# Sanity0.net
KiCad netlist of a schematic drawn in Altium Designer
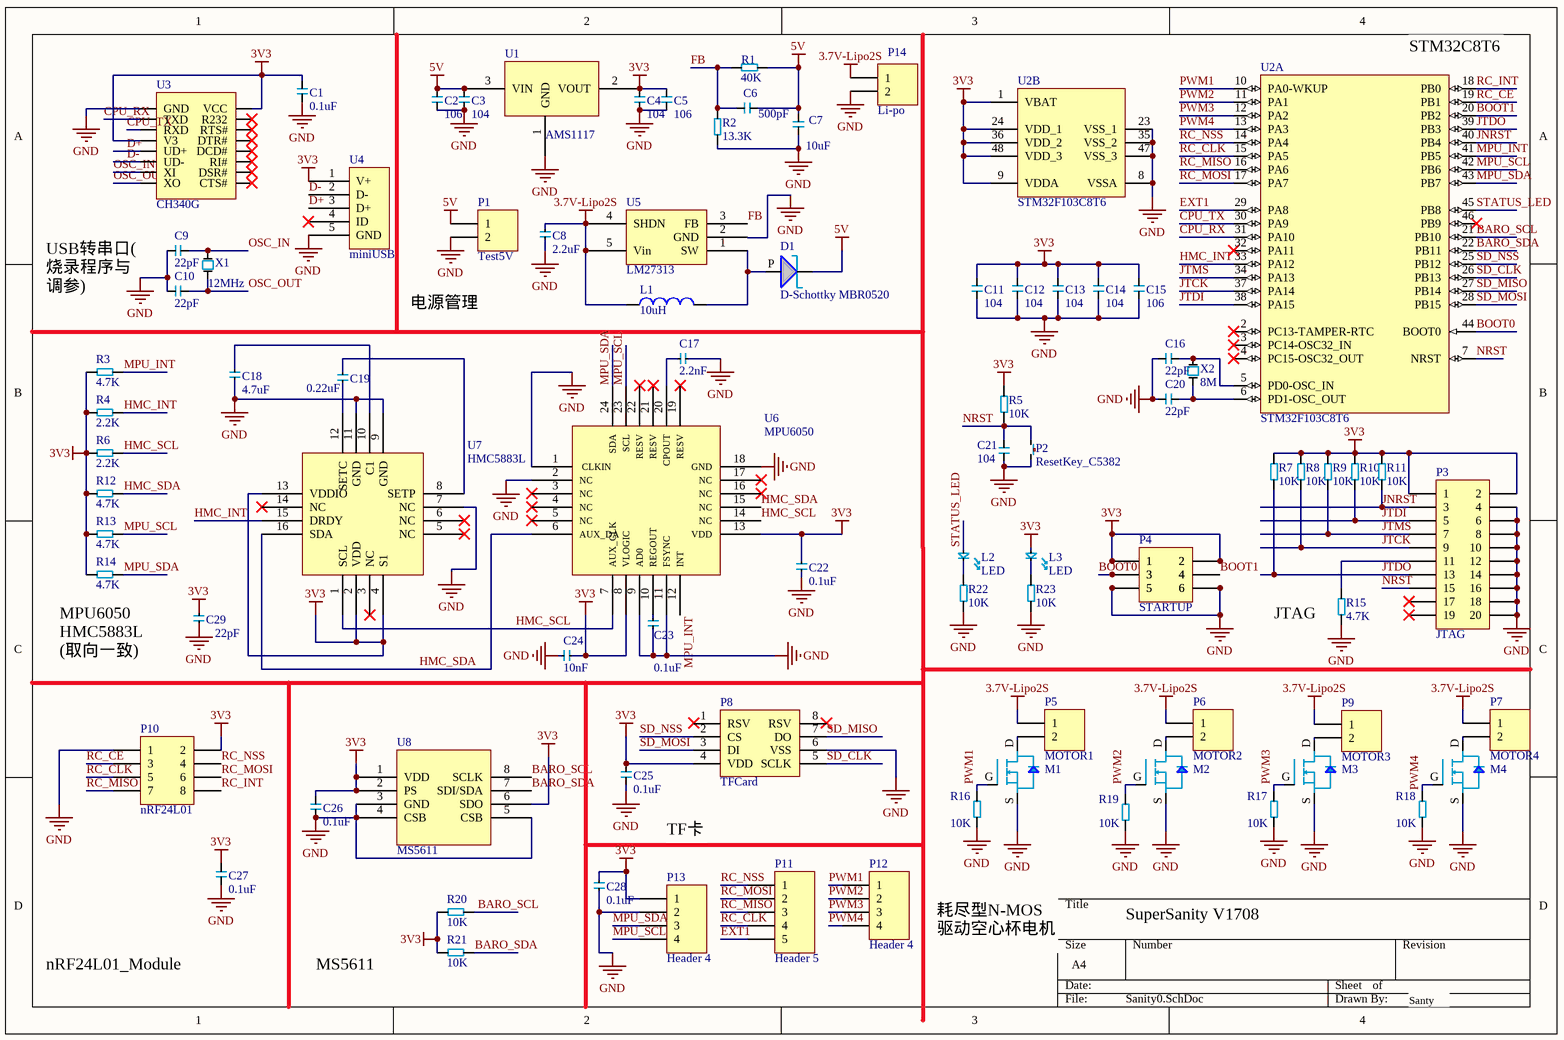
[diagram p0: Sanity0.SchDoc]

(export (version "E")
  (design (tool "Eeschema 10.0.6"))
  (components
    (comp (ref "C1") (value "0.1uF") (footprint "LC-0402") (libsource (lib "0402") (part "Cap-0402")))
    (comp (ref "C2") (value "106") (footprint "LC-0402") (libsource (lib "0402") (part "Cap-0402")))
    (comp (ref "C3") (value "104") (footprint "LC-0402") (libsource (lib "0402") (part "Cap-0402")))
    (comp (ref "C4") (value "104") (footprint "LC-0402") (libsource (lib "0402") (part "Cap-0402")))
    (comp (ref "C5") (value "106") (footprint "LC-0402") (libsource (lib "0402") (part "Cap-0402")))
    (comp (ref "C6") (value "500pF") (footprint "LC-0402") (libsource (lib "0402") (part "Cap-0402")))
    (comp (ref "C7") (value "10uF") (footprint "LC-0402") (libsource (lib "0402") (part "Cap-0402")))
    (comp (ref "C8") (value "2.2uF") (footprint "Cap-0603") (libsource (lib "Cap-0603") (part "Cap0603")))
    (comp (ref "C9") (value "22pF") (footprint "LC-0402") (libsource (lib "0402") (part "Cap-0402")))
    (comp (ref "C10") (value "22pF") (footprint "LC-0402") (libsource (lib "0402") (part "Cap-0402")))
    (comp (ref "C11") (value "104") (footprint "LC-0402") (libsource (lib "0402") (part "Cap-0402")))
    (comp (ref "C12") (value "104") (footprint "LC-0402") (libsource (lib "0402") (part "Cap-0402")))
    (comp (ref "C13") (value "104") (footprint "LC-0402") (libsource (lib "0402") (part "Cap-0402")))
    (comp (ref "C14") (value "104") (footprint "LC-0402") (libsource (lib "0402") (part "Cap-0402")))
    (comp (ref "C15") (value "106") (footprint "LC-0402") (libsource (lib "0402") (part "Cap-0402")))
    (comp (ref "C16") (value "22pF") (footprint "LC-0402") (libsource (lib "0402") (part "Cap-0402")))
    (comp (ref "C17") (value "2.2nF") (footprint "Cap-0603") (libsource (lib "Cap-0603") (part "Cap0603")))
    (comp (ref "C18") (value "4.7uF") (footprint "Cap-0603") (libsource (lib "Cap-0603") (part "Cap0603")))
    (comp (ref "C19") (value "0.22uF") (footprint "Cap-0603") (libsource (lib "Cap-0603") (part "Cap0603")))
    (comp (ref "C20") (value "22pF") (footprint "LC-0402") (libsource (lib "0402") (part "Cap-0402")))
    (comp (ref "C21") (value "104") (footprint "LC-0402") (libsource (lib "0402") (part "Cap-0402")))
    (comp (ref "C22") (value "0.1uF") (footprint "Cap-0603") (libsource (lib "Cap-0603") (part "Cap0603")))
    (comp (ref "C23") (value "0.1uF") (footprint "Cap-0603") (libsource (lib "Cap-0603") (part "Cap0603")))
    (comp (ref "C24") (value "10nF") (footprint "Cap-0603") (libsource (lib "Cap-0603") (part "Cap0603")))
    (comp (ref "C25") (value "0.1uF") (footprint "LC-0402") (libsource (lib "0402") (part "Cap-0402")))
    (comp (ref "C26") (value "0.1uF") (footprint "LC-0402") (libsource (lib "0402") (part "Cap-0402")))
    (comp (ref "C27") (value "0.1uF") (footprint "LC-0402") (libsource (lib "0402") (part "Cap-0402")))
    (comp (ref "C28") (value "0.1uF") (footprint "Cap-0603") (libsource (lib "Cap-0603") (part "Cap0603")))
    (comp (ref "C29") (value "22pF") (footprint "Cap-0603") (libsource (lib "Cap-0603") (part "Cap0603")))
    (comp (ref "D1")
      (value "D-Schottky MBR0520")
      (footprint "SOD123")
      (libsource (lib "D-Schottky-MBR0520") (part "D-Schottky MBR0520"))
    )
    (comp (ref "L1")
      (value "10uH")
      (footprint "INDC1608L")
      (description "Inductor")
      (fields (field (name "PUBLISHER") "Altium Limited"))
      (libsource (lib "Miscellaneous Devices") (part "Inductor"))
    )
    (comp (ref "L2") (value "LED") (footprint "0603_LED_S1") (libsource (lib "LED_0603") (part "LED")))
    (comp (ref "L3") (value "LED") (footprint "0603_LED_S1") (libsource (lib "LED_0603") (part "LED")))
    (comp (ref "M1")
      (value "SI2302-NMOS")
      (footprint "SOT-23(SOT-23-3)")
      (libsource (lib "SI2303-NMOS") (part "SI2302-NMOS"))
    )
    (comp (ref "M2")
      (value "SI2302-NMOS")
      (footprint "SOT-23(SOT-23-3)")
      (libsource (lib "SI2303-NMOS") (part "SI2302-NMOS"))
    )
    (comp (ref "M3")
      (value "SI2302-NMOS")
      (footprint "SOT-23(SOT-23-3)")
      (libsource (lib "SI2303-NMOS") (part "SI2302-NMOS"))
    )
    (comp (ref "M4")
      (value "SI2302-NMOS")
      (footprint "SOT-23(SOT-23-3)")
      (libsource (lib "SI2303-NMOS") (part "SI2302-NMOS"))
    )
    (comp (ref "P1")
      (value "Test5V")
      (footprint "HDR1X2")
      (description "Header, 2-Pin")
      (fields (field (name "PUBLISHER") "Altium Limited"))
      (libsource (lib "Miscellaneous Connectors") (part "Header 2"))
    )
    (comp (ref "P2")
      (value "ResetKey_C5382")
      (footprint "ResetKeyC5382")
      (libsource (lib "ResetKey_C5382") (part "ResetKey_C5382"))
    )
    (comp (ref "P3")
      (value "JTAG")
      (footprint "HDR2X10")
      (description "Header, 10-Pin, Dual row")
      (fields (field (name "PUBLISHER") "Altium Limited"))
      (libsource (lib "Miscellaneous Connectors") (part "Header 10X2"))
    )
    (comp (ref "P4")
      (value "STARTUP")
      (footprint "HDR2X3")
      (description "Header, 3-Pin, Dual row")
      (fields (field (name "PUBLISHER") "Altium Limited"))
      (libsource (lib "Miscellaneous Connectors") (part "Header 3X2"))
    )
    (comp (ref "P5")
      (value "MOTOR1")
      (footprint "HDR1X2")
      (description "Header, 2-Pin")
      (fields (field (name "PUBLISHER") "Altium Limited"))
      (libsource (lib "Miscellaneous Connectors") (part "Header 2"))
    )
    (comp (ref "P6")
      (value "MOTOR2")
      (footprint "HDR1X2")
      (description "Header, 2-Pin")
      (fields (field (name "PUBLISHER") "Altium Limited"))
      (libsource (lib "Miscellaneous Connectors") (part "Header 2"))
    )
    (comp (ref "P7")
      (value "MOTOR4")
      (footprint "HDR1X2")
      (description "Header, 2-Pin")
      (fields (field (name "PUBLISHER") "Altium Limited"))
      (libsource (lib "Miscellaneous Connectors") (part "Header 2"))
    )
    (comp (ref "P8") (value "TFCard") (footprint "TF_card") (libsource (lib "TF_card") (part "TFCard")))
    (comp (ref "P9")
      (value "MOTOR3")
      (footprint "HDR1X2")
      (description "Header, 2-Pin")
      (fields (field (name "PUBLISHER") "Altium Limited"))
      (libsource (lib "Miscellaneous Connectors") (part "Header 2"))
    )
    (comp (ref "P10")
      (value "nRF24L01")
      (footprint "HDR2X4")
      (description "Header, 4-Pin, Dual row")
      (fields (field (name "PUBLISHER") "Altium Limited"))
      (libsource (lib "Miscellaneous Connectors") (part "Header 4X2"))
    )
    (comp (ref "P11")
      (value "Header 5")
      (footprint "HDR1X5")
      (description "Header, 5-Pin")
      (fields (field (name "PUBLISHER") "Altium Limited"))
      (libsource (lib "Miscellaneous Connectors") (part "Header 5"))
    )
    (comp (ref "P12")
      (value "Header 4")
      (footprint "HDR1X4")
      (description "Header, 4-Pin")
      (fields (field (name "PUBLISHER") "Altium Limited"))
      (libsource (lib "Miscellaneous Connectors") (part "Header 4"))
    )
    (comp (ref "P13")
      (value "Header 4")
      (footprint "HDR1X4")
      (description "Header, 4-Pin")
      (fields (field (name "PUBLISHER") "Altium Limited"))
      (libsource (lib "Miscellaneous Connectors") (part "Header 4"))
    )
    (comp (ref "P14")
      (value "Li-po")
      (footprint "HDR1X2")
      (description "Header, 2-Pin")
      (fields (field (name "PUBLISHER") "Altium Limited"))
      (libsource (lib "Miscellaneous Connectors") (part "Header 2"))
    )
    (comp (ref "R1") (value "40K") (footprint "Res-0402") (libsource (lib "0402-Res") (part "Res-0402")))
    (comp (ref "R2") (value "13.3K") (footprint "Res-0402") (libsource (lib "0402-Res") (part "Res-0402")))
    (comp (ref "R3") (value "4.7K") (footprint "Res-0402") (libsource (lib "0402-Res") (part "Res-0402")))
    (comp (ref "R4") (value "2.2K") (footprint "Res-0402") (libsource (lib "0402-Res") (part "Res-0402")))
    (comp (ref "R5") (value "10K") (footprint "Res-0402") (libsource (lib "0402-Res") (part "Res-0402")))
    (comp (ref "R6") (value "2.2K") (footprint "Res-0402") (libsource (lib "0402-Res") (part "Res-0402")))
    (comp (ref "R7") (value "10K") (footprint "Res-0402") (libsource (lib "0402-Res") (part "Res-0402")))
    (comp (ref "R8") (value "10K") (footprint "Res-0402") (libsource (lib "0402-Res") (part "Res-0402")))
    (comp (ref "R9") (value "10K") (footprint "Res-0402") (libsource (lib "0402-Res") (part "Res-0402")))
    (comp (ref "R10") (value "10K") (footprint "Res-0402") (libsource (lib "0402-Res") (part "Res-0402")))
    (comp (ref "R11") (value "10K") (footprint "Res-0402") (libsource (lib "0402-Res") (part "Res-0402")))
    (comp (ref "R12") (value "4.7K") (footprint "Res-0402") (libsource (lib "0402-Res") (part "Res-0402")))
    (comp (ref "R13") (value "4.7K") (footprint "Res-0402") (libsource (lib "0402-Res") (part "Res-0402")))
    (comp (ref "R14") (value "4.7K") (footprint "Res-0402") (libsource (lib "0402-Res") (part "Res-0402")))
    (comp (ref "R15") (value "4.7K") (footprint "Res-0402") (libsource (lib "0402-Res") (part "Res-0402")))
    (comp (ref "R16") (value "10K") (footprint "Res-0402") (libsource (lib "0402-Res") (part "Res-0402")))
    (comp (ref "R17") (value "10K") (footprint "Res-0402") (libsource (lib "0402-Res") (part "Res-0402")))
    (comp (ref "R18") (value "10K") (footprint "Res-0402") (libsource (lib "0402-Res") (part "Res-0402")))
    (comp (ref "R19") (value "10K") (footprint "Res-0402") (libsource (lib "0402-Res") (part "Res-0402")))
    (comp (ref "R20") (value "10K") (footprint "Res-0402") (libsource (lib "0402-Res") (part "Res-0402")))
    (comp (ref "R21") (value "10K") (footprint "Res-0402") (libsource (lib "0402-Res") (part "Res-0402")))
    (comp (ref "R22") (value "10K") (footprint "Res-0402") (libsource (lib "0402-Res") (part "Res-0402")))
    (comp (ref "R23") (value "10K") (footprint "Res-0402") (libsource (lib "0402-Res") (part "Res-0402")))
    (comp (ref "U1") (value "AMS1117") (footprint "AMS1117") (libsource (lib "AMS1117") (part "AMS1117")))
    (comp (ref "U2")
      (value "STM32F103C8T6")
      (footprint "STM-LQFP48_N")
      (libsource (lib "STMicroelectronics STM32 F1") (part "STM32F103C8T6"))
    )
    (comp (ref "U3")
      (value "CH340G")
      (footprint "LC-SOP-16_150mil")
      (libsource (lib "CH340G") (part "CH340G"))
    )
    (comp (ref "U4") (value "miniUSB") (footprint "miniUSB") (libsource (lib "miniUSB") (part "miniUSB")))
    (comp (ref "U5") (value "LM27313") (footprint "LM27313") (libsource (lib "LM27313") (part "LM27313")))
    (comp (ref "U6") (value "MPU6050") (footprint "MPU6050") (libsource (lib "MPU6050") (part "MPU6050")))
    (comp (ref "U7")
      (value "HMC5883L")
      (footprint "LCCS50P300X300X90-16N-1")
      (libsource (lib "HMC5883L") (part "HMC5883L"))
    )
    (comp (ref "U8") (value "MS5611") (footprint "MS5611") (libsource (lib "MS5611") (part "MS5611")))
    (comp (ref "X1") (value "12MHz") (footprint "LC-HC-49SMD") (libsource (lib "49SMD-8M") (part "49SMD")))
    (comp (ref "X2") (value "8M") (footprint "LC-HC-49SMD") (libsource (lib "49SMD-8M") (part "49SMD")))
  )
  (nets
    (net (code "1") (name "/BARO_SCL") (class "Default")
      (node (ref "R20") (pin "1") (pinfunction "1_1") (pintype "passive"))
      (node (ref "U2") (pin "21") (pinfunction "PB10_21") (pintype "bidirectional"))
      (node (ref "U8") (pin "8") (pinfunction "SCLK_8") (pintype "passive"))
    )
    (net (code "2") (name "/BARO_SDA") (class "Default")
      (node (ref "R21") (pin "1") (pinfunction "1_1") (pintype "passive"))
      (node (ref "U2") (pin "22") (pinfunction "PB11_22") (pintype "bidirectional"))
      (node (ref "U8") (pin "7") (pinfunction "SDI/SDA_7") (pintype "passive"))
    )
    (net (code "3") (name "/BOOT0") (class "Default")
      (node (ref "P4") (pin "3") (pinfunction "3_3") (pintype "passive"))
      (node (ref "U2") (pin "44") (pinfunction "BOOT0_44") (pintype "input"))
    )
    (net (code "4") (name "/BOOT1") (class "Default")
      (node (ref "P4") (pin "4") (pinfunction "4_4") (pintype "passive"))
      (node (ref "U2") (pin "20") (pinfunction "PB2_20") (pintype "bidirectional"))
    )
    (net (code "5") (name "/CPU_RX") (class "Default")
      (node (ref "U2") (pin "31") (pinfunction "PA10_31") (pintype "bidirectional"))
      (node (ref "U3") (pin "2") (pinfunction "TXD_2") (pintype "passive"))
    )
    (net (code "6") (name "/CPU_TX") (class "Default")
      (node (ref "U2") (pin "30") (pinfunction "PA9_30") (pintype "bidirectional"))
      (node (ref "U3") (pin "3") (pinfunction "RXD_3") (pintype "passive"))
    )
    (net (code "7") (name "/D+") (class "Default")
      (node (ref "U3") (pin "5") (pinfunction "UD+_5") (pintype "passive"))
      (node (ref "U4") (pin "3") (pinfunction "D+_3") (pintype "passive"))
    )
    (net (code "8") (name "/D-") (class "Default")
      (node (ref "U3") (pin "6") (pinfunction "UD-_6") (pintype "passive"))
      (node (ref "U4") (pin "2") (pinfunction "D-_2") (pintype "passive"))
    )
    (net (code "9") (name "/EXT1") (class "Default")
      (node (ref "P11") (pin "5") (pinfunction "5_5") (pintype "passive"))
      (node (ref "U2") (pin "29") (pinfunction "PA8_29") (pintype "bidirectional"))
    )
    (net (code "10") (name "/FB") (class "Default")
      (node (ref "C6") (pin "0") (pinfunction "0_0") (pintype "passive"))
      (node (ref "R1") (pin "1") (pinfunction "1_1") (pintype "passive"))
      (node (ref "R2") (pin "0") (pinfunction "0_0") (pintype "passive"))
      (node (ref "U5") (pin "3") (pinfunction "FB_3") (pintype "passive"))
    )
    (net (code "11") (name "/HMC_INT") (class "Default")
      (node (ref "R4") (pin "1") (pinfunction "1_1") (pintype "passive"))
      (node (ref "U2") (pin "33") (pinfunction "PA12_33") (pintype "bidirectional"))
      (node (ref "U7") (pin "15") (pinfunction "DRDY_15") (pintype "passive"))
    )
    (net (code "12") (name "/HMC_SCL") (class "Default")
      (node (ref "R6") (pin "1") (pinfunction "1_1") (pintype "passive"))
      (node (ref "U6") (pin "14") (pinfunction "NC_14") (pintype "passive"))
      (node (ref "U6") (pin "7") (pinfunction "AUX_CLK_7") (pintype "passive"))
      (node (ref "U7") (pin "1") (pinfunction "SCL_1") (pintype "passive"))
    )
    (net (code "13") (name "/HMC_SDA") (class "Default")
      (node (ref "R12") (pin "1") (pinfunction "1_1") (pintype "passive"))
      (node (ref "U6") (pin "15") (pinfunction "NC_15") (pintype "passive"))
      (node (ref "U6") (pin "6") (pinfunction "AUX_DA_6") (pintype "passive"))
      (node (ref "U7") (pin "16") (pinfunction "SDA_16") (pintype "passive"))
    )
    (net (code "14") (name "/JNRST") (class "Default")
      (node (ref "P3") (pin "3") (pinfunction "3_3") (pintype "passive"))
      (node (ref "R11") (pin "1") (pinfunction "1_1") (pintype "passive"))
      (node (ref "U2") (pin "40") (pinfunction "PB4_40") (pintype "bidirectional"))
    )
    (net (code "15") (name "/JTCK") (class "Default")
      (node (ref "P3") (pin "9") (pinfunction "9_9") (pintype "passive"))
      (node (ref "R8") (pin "1") (pinfunction "1_1") (pintype "passive"))
      (node (ref "U2") (pin "37") (pinfunction "PA14_37") (pintype "bidirectional"))
    )
    (net (code "16") (name "/JTDI") (class "Default")
      (node (ref "P3") (pin "5") (pinfunction "5_5") (pintype "passive"))
      (node (ref "R10") (pin "1") (pinfunction "1_1") (pintype "passive"))
      (node (ref "U2") (pin "38") (pinfunction "PA15_38") (pintype "bidirectional"))
    )
    (net (code "17") (name "/JTDO") (class "Default")
      (node (ref "P3") (pin "13") (pinfunction "13_13") (pintype "passive"))
      (node (ref "R7") (pin "1") (pinfunction "1_1") (pintype "passive"))
      (node (ref "U2") (pin "39") (pinfunction "PB3_39") (pintype "bidirectional"))
    )
    (net (code "18") (name "/JTMS") (class "Default")
      (node (ref "P3") (pin "7") (pinfunction "7_7") (pintype "passive"))
      (node (ref "R9") (pin "1") (pinfunction "1_1") (pintype "passive"))
      (node (ref "U2") (pin "34") (pinfunction "PA13_34") (pintype "bidirectional"))
    )
    (net (code "19") (name "/MPU_INT") (class "Default")
      (node (ref "R3") (pin "1") (pinfunction "1_1") (pintype "passive"))
      (node (ref "U2") (pin "41") (pinfunction "PB5_41") (pintype "bidirectional"))
      (node (ref "U6") (pin "12") (pinfunction "INT_12") (pintype "passive"))
    )
    (net (code "20") (name "/MPU_SCL") (class "Default")
      (node (ref "P13") (pin "4") (pinfunction "4_4") (pintype "passive"))
      (node (ref "R13") (pin "1") (pinfunction "1_1") (pintype "passive"))
      (node (ref "U2") (pin "42") (pinfunction "PB6_42") (pintype "bidirectional"))
      (node (ref "U6") (pin "23") (pinfunction "SCL_23") (pintype "passive"))
    )
    (net (code "21") (name "/MPU_SDA") (class "Default")
      (node (ref "P13") (pin "3") (pinfunction "3_3") (pintype "passive"))
      (node (ref "R14") (pin "1") (pinfunction "1_1") (pintype "passive"))
      (node (ref "U2") (pin "43") (pinfunction "PB7_43") (pintype "bidirectional"))
      (node (ref "U6") (pin "24") (pinfunction "SDA_24") (pintype "passive"))
    )
    (net (code "22") (name "/NRST") (class "Default")
      (node (ref "C21") (pin "1") (pinfunction "1_1") (pintype "passive"))
      (node (ref "P2") (pin "1") (pinfunction "1_1") (pintype "passive"))
      (node (ref "P3") (pin "15") (pinfunction "15_15") (pintype "passive"))
      (node (ref "R5") (pin "1") (pinfunction "1_1") (pintype "passive"))
      (node (ref "U2") (pin "7") (pinfunction "NRST_7") (pintype "bidirectional"))
    )
    (net (code "23") (name "/OSC_IN") (class "Default")
      (node (ref "C9") (pin "0") (pinfunction "0_0") (pintype "passive"))
      (node (ref "U3") (pin "7") (pinfunction "XI_7") (pintype "passive"))
      (node (ref "X1") (pin "0") (pinfunction "0_0") (pintype "passive"))
    )
    (net (code "24") (name "/OSC_OUT") (class "Default")
      (node (ref "C10") (pin "0") (pinfunction "0_0") (pintype "passive"))
      (node (ref "U3") (pin "8") (pinfunction "XO_8") (pintype "passive"))
      (node (ref "X1") (pin "1") (pinfunction "1_1") (pintype "passive"))
    )
    (net (code "25") (name "/PWM1") (class "Default")
      (node (ref "M1") (pin "G") (pinfunction "2_G") (pintype "passive"))
      (node (ref "P12") (pin "1") (pinfunction "1_1") (pintype "passive"))
      (node (ref "R16") (pin "0") (pinfunction "0_0") (pintype "passive"))
      (node (ref "U2") (pin "10") (pinfunction "PA0-WKUP_10") (pintype "bidirectional"))
    )
    (net (code "26") (name "/PWM2") (class "Default")
      (node (ref "M2") (pin "G") (pinfunction "2_G") (pintype "passive"))
      (node (ref "P12") (pin "2") (pinfunction "2_2") (pintype "passive"))
      (node (ref "R19") (pin "1") (pinfunction "1_1") (pintype "passive"))
      (node (ref "U2") (pin "11") (pinfunction "PA1_11") (pintype "bidirectional"))
    )
    (net (code "27") (name "/PWM3") (class "Default")
      (node (ref "M3") (pin "G") (pinfunction "2_G") (pintype "passive"))
      (node (ref "P12") (pin "3") (pinfunction "3_3") (pintype "passive"))
      (node (ref "R17") (pin "0") (pinfunction "0_0") (pintype "passive"))
      (node (ref "U2") (pin "12") (pinfunction "PA2_12") (pintype "bidirectional"))
    )
    (net (code "28") (name "/PWM4") (class "Default")
      (node (ref "M4") (pin "G") (pinfunction "2_G") (pintype "passive"))
      (node (ref "P12") (pin "4") (pinfunction "4_4") (pintype "passive"))
      (node (ref "R18") (pin "1") (pinfunction "1_1") (pintype "passive"))
      (node (ref "U2") (pin "13") (pinfunction "PA3_13") (pintype "bidirectional"))
    )
    (net (code "29") (name "/RC_CE") (class "Default")
      (node (ref "P10") (pin "3") (pinfunction "3_3") (pintype "passive"))
      (node (ref "U2") (pin "19") (pinfunction "PB1_19") (pintype "bidirectional"))
    )
    (net (code "30") (name "/RC_CLK") (class "Default")
      (node (ref "P10") (pin "5") (pinfunction "5_5") (pintype "passive"))
      (node (ref "P11") (pin "4") (pinfunction "4_4") (pintype "passive"))
      (node (ref "U2") (pin "15") (pinfunction "PA5_15") (pintype "bidirectional"))
    )
    (net (code "31") (name "/RC_INT") (class "Default")
      (node (ref "P10") (pin "8") (pinfunction "8_8") (pintype "passive"))
      (node (ref "U2") (pin "18") (pinfunction "PB0_18") (pintype "bidirectional"))
    )
    (net (code "32") (name "/RC_MISO") (class "Default")
      (node (ref "P10") (pin "7") (pinfunction "7_7") (pintype "passive"))
      (node (ref "P11") (pin "3") (pinfunction "3_3") (pintype "passive"))
      (node (ref "U2") (pin "16") (pinfunction "PA6_16") (pintype "bidirectional"))
    )
    (net (code "33") (name "/RC_MOSI") (class "Default")
      (node (ref "P10") (pin "6") (pinfunction "6_6") (pintype "passive"))
      (node (ref "P11") (pin "2") (pinfunction "2_2") (pintype "passive"))
      (node (ref "U2") (pin "17") (pinfunction "PA7_17") (pintype "bidirectional"))
    )
    (net (code "34") (name "/RC_NSS") (class "Default")
      (node (ref "P10") (pin "4") (pinfunction "4_4") (pintype "passive"))
      (node (ref "P11") (pin "1") (pinfunction "1_1") (pintype "passive"))
      (node (ref "U2") (pin "14") (pinfunction "PA4_14") (pintype "bidirectional"))
    )
    (net (code "35") (name "/SD_CLK") (class "Default")
      (node (ref "P8") (pin "5") (pinfunction "SCLK_5") (pintype "passive"))
      (node (ref "U2") (pin "26") (pinfunction "PB13_26") (pintype "bidirectional"))
    )
    (net (code "36") (name "/SD_MISO") (class "Default")
      (node (ref "P8") (pin "7") (pinfunction "DO_7") (pintype "passive"))
      (node (ref "U2") (pin "27") (pinfunction "PB14_27") (pintype "bidirectional"))
    )
    (net (code "37") (name "/SD_MOSI") (class "Default")
      (node (ref "P8") (pin "3") (pinfunction "DI_3") (pintype "passive"))
      (node (ref "U2") (pin "28") (pinfunction "PB15_28") (pintype "bidirectional"))
    )
    (net (code "38") (name "/SD_NSS") (class "Default")
      (node (ref "P8") (pin "2") (pinfunction "CS_2") (pintype "passive"))
      (node (ref "U2") (pin "25") (pinfunction "PB12_25") (pintype "bidirectional"))
    )
    (net (code "39") (name "/STATUS_LED") (class "Default")
      (node (ref "L2") (pin "P") (pinfunction "1_P") (pintype "passive"))
      (node (ref "U2") (pin "45") (pinfunction "PB8_45") (pintype "bidirectional"))
    )
    (net (code "40") (name "3.7V-Lipo2S") (class "Default")
      (node (ref "C8") (pin "1") (pinfunction "1_1") (pintype "passive"))
      (node (ref "L1") (pin "1") (pinfunction "1_1") (pintype "passive"))
      (node (ref "P14") (pin "1") (pinfunction "1_1") (pintype "passive"))
      (node (ref "P5") (pin "1") (pinfunction "1_1") (pintype "passive"))
      (node (ref "P6") (pin "1") (pinfunction "1_1") (pintype "passive"))
      (node (ref "P7") (pin "1") (pinfunction "1_1") (pintype "passive"))
      (node (ref "P9") (pin "1") (pinfunction "1_1") (pintype "passive"))
      (node (ref "U5") (pin "4") (pinfunction "SHDN_4") (pintype "passive"))
      (node (ref "U5") (pin "5") (pinfunction "Vin_5") (pintype "passive"))
    )
    (net (code "41") (name "3V3") (class "Default")
      (node (ref "C1") (pin "1") (pinfunction "1_1") (pintype "passive"))
      (node (ref "C11") (pin "0") (pinfunction "0_0") (pintype "passive"))
      (node (ref "C12") (pin "1") (pinfunction "1_1") (pintype "passive"))
      (node (ref "C13") (pin "1") (pinfunction "1_1") (pintype "passive"))
      (node (ref "C14") (pin "1") (pinfunction "1_1") (pintype "passive"))
      (node (ref "C15") (pin "1") (pinfunction "1_1") (pintype "passive"))
      (node (ref "C22") (pin "1") (pinfunction "1_1") (pintype "passive"))
      (node (ref "C24") (pin "1") (pinfunction "1_1") (pintype "passive"))
      (node (ref "C25") (pin "1") (pinfunction "1_1") (pintype "passive"))
      (node (ref "C26") (pin "1") (pinfunction "1_1") (pintype "passive"))
      (node (ref "C27") (pin "1") (pinfunction "1_1") (pintype "passive"))
      (node (ref "C28") (pin "1") (pinfunction "1_1") (pintype "passive"))
      (node (ref "C29") (pin "1") (pinfunction "1_1") (pintype "passive"))
      (node (ref "C4") (pin "1") (pinfunction "1_1") (pintype "passive"))
      (node (ref "C5") (pin "1") (pinfunction "1_1") (pintype "passive"))
      (node (ref "L3") (pin "P") (pinfunction "1_P") (pintype "passive"))
      (node (ref "P10") (pin "2") (pinfunction "2_2") (pintype "passive"))
      (node (ref "P13") (pin "1") (pinfunction "1_1") (pintype "passive"))
      (node (ref "P3") (pin "1") (pinfunction "1_1") (pintype "passive"))
      (node (ref "P3") (pin "2") (pinfunction "2_2") (pintype "passive"))
      (node (ref "P4") (pin "1") (pinfunction "1_1") (pintype "passive"))
      (node (ref "P4") (pin "2") (pinfunction "2_2") (pintype "passive"))
      (node (ref "P8") (pin "4") (pinfunction "VDD_4") (pintype "passive"))
      (node (ref "R10") (pin "0") (pinfunction "0_0") (pintype "passive"))
      (node (ref "R11") (pin "0") (pinfunction "0_0") (pintype "passive"))
      (node (ref "R12") (pin "0") (pinfunction "0_0") (pintype "passive"))
      (node (ref "R13") (pin "0") (pinfunction "0_0") (pintype "passive"))
      (node (ref "R14") (pin "0") (pinfunction "0_0") (pintype "passive"))
      (node (ref "R20") (pin "0") (pinfunction "0_0") (pintype "passive"))
      (node (ref "R21") (pin "0") (pinfunction "0_0") (pintype "passive"))
      (node (ref "R3") (pin "0") (pinfunction "0_0") (pintype "passive"))
      (node (ref "R4") (pin "0") (pinfunction "0_0") (pintype "passive"))
      (node (ref "R5") (pin "0") (pinfunction "0_0") (pintype "passive"))
      (node (ref "R6") (pin "0") (pinfunction "0_0") (pintype "passive"))
      (node (ref "R7") (pin "0") (pinfunction "0_0") (pintype "passive"))
      (node (ref "R8") (pin "0") (pinfunction "0_0") (pintype "passive"))
      (node (ref "R9") (pin "0") (pinfunction "0_0") (pintype "passive"))
      (node (ref "U1") (pin "2") (pinfunction "VOUT_2") (pintype "passive"))
      (node (ref "U2") (pin "1") (pinfunction "VBAT_1") (pintype "power_in"))
      (node (ref "U2") (pin "24") (pinfunction "VDD_1_24") (pintype "power_in"))
      (node (ref "U2") (pin "36") (pinfunction "VDD_2_36") (pintype "power_in"))
      (node (ref "U2") (pin "48") (pinfunction "VDD_3_48") (pintype "power_in"))
      (node (ref "U2") (pin "9") (pinfunction "VDDA_9") (pintype "power_in"))
      (node (ref "U3") (pin "16") (pinfunction "VCC_16") (pintype "passive"))
      (node (ref "U3") (pin "4") (pinfunction "V3_4") (pintype "passive"))
      (node (ref "U4") (pin "1") (pinfunction "V+_1") (pintype "passive"))
      (node (ref "U6") (pin "13") (pinfunction "VDD_13") (pintype "passive"))
      (node (ref "U6") (pin "8") (pinfunction "VLOGIC_8") (pintype "passive"))
      (node (ref "U7") (pin "13") (pinfunction "VDDIO_13") (pintype "passive"))
      (node (ref "U7") (pin "2") (pinfunction "VDD_2") (pintype "passive"))
      (node (ref "U7") (pin "4") (pinfunction "S1_4") (pintype "passive"))
      (node (ref "U8") (pin "1") (pinfunction "VDD_1") (pintype "passive"))
      (node (ref "U8") (pin "2") (pinfunction "PS_2") (pintype "passive"))
      (node (ref "U8") (pin "6") (pinfunction "SDO_6") (pintype "passive"))
    )
    (net (code "42") (name "5V") (class "Default")
      (node (ref "C2") (pin "1") (pinfunction "1_1") (pintype "passive"))
      (node (ref "C3") (pin "1") (pinfunction "1_1") (pintype "passive"))
      (node (ref "C6") (pin "1") (pinfunction "1_1") (pintype "passive"))
      (node (ref "C7") (pin "1") (pinfunction "1_1") (pintype "passive"))
      (node (ref "D1") (pin "N") (pinfunction "N_N") (pintype "passive"))
      (node (ref "P1") (pin "1") (pinfunction "1_1") (pintype "passive"))
      (node (ref "R1") (pin "0") (pinfunction "0_0") (pintype "passive"))
      (node (ref "U1") (pin "3") (pinfunction "VIN_3") (pintype "passive"))
    )
    (net (code "43") (name "GND") (class "Default")
      (node (ref "C1") (pin "0") (pinfunction "0_0") (pintype "passive"))
      (node (ref "C10") (pin "1") (pinfunction "1_1") (pintype "passive"))
      (node (ref "C11") (pin "1") (pinfunction "1_1") (pintype "passive"))
      (node (ref "C12") (pin "0") (pinfunction "0_0") (pintype "passive"))
      (node (ref "C13") (pin "0") (pinfunction "0_0") (pintype "passive"))
      (node (ref "C14") (pin "0") (pinfunction "0_0") (pintype "passive"))
      (node (ref "C15") (pin "0") (pinfunction "0_0") (pintype "passive"))
      (node (ref "C16") (pin "0") (pinfunction "0_0") (pintype "passive"))
      (node (ref "C17") (pin "1") (pinfunction "1_1") (pintype "passive"))
      (node (ref "C18") (pin "2") (pinfunction "2_2") (pintype "passive"))
      (node (ref "C2") (pin "0") (pinfunction "0_0") (pintype "passive"))
      (node (ref "C20") (pin "0") (pinfunction "0_0") (pintype "passive"))
      (node (ref "C21") (pin "0") (pinfunction "0_0") (pintype "passive"))
      (node (ref "C22") (pin "2") (pinfunction "2_2") (pintype "passive"))
      (node (ref "C23") (pin "2") (pinfunction "2_2") (pintype "passive"))
      (node (ref "C24") (pin "2") (pinfunction "2_2") (pintype "passive"))
      (node (ref "C25") (pin "0") (pinfunction "0_0") (pintype "passive"))
      (node (ref "C26") (pin "0") (pinfunction "0_0") (pintype "passive"))
      (node (ref "C27") (pin "0") (pinfunction "0_0") (pintype "passive"))
      (node (ref "C28") (pin "2") (pinfunction "2_2") (pintype "passive"))
      (node (ref "C29") (pin "2") (pinfunction "2_2") (pintype "passive"))
      (node (ref "C3") (pin "0") (pinfunction "0_0") (pintype "passive"))
      (node (ref "C4") (pin "0") (pinfunction "0_0") (pintype "passive"))
      (node (ref "C5") (pin "0") (pinfunction "0_0") (pintype "passive"))
      (node (ref "C7") (pin "0") (pinfunction "0_0") (pintype "passive"))
      (node (ref "C8") (pin "2") (pinfunction "2_2") (pintype "passive"))
      (node (ref "C9") (pin "1") (pinfunction "1_1") (pintype "passive"))
      (node (ref "M1") (pin "S") (pinfunction "1_S") (pintype "passive"))
      (node (ref "M2") (pin "S") (pinfunction "1_S") (pintype "passive"))
      (node (ref "M3") (pin "S") (pinfunction "1_S") (pintype "passive"))
      (node (ref "M4") (pin "S") (pinfunction "1_S") (pintype "passive"))
      (node (ref "P1") (pin "2") (pinfunction "2_2") (pintype "passive"))
      (node (ref "P10") (pin "1") (pinfunction "1_1") (pintype "passive"))
      (node (ref "P13") (pin "2") (pinfunction "2_2") (pintype "passive"))
      (node (ref "P14") (pin "2") (pinfunction "2_2") (pintype "passive"))
      (node (ref "P2") (pin "0") (pinfunction "0_0") (pintype "passive"))
      (node (ref "P3") (pin "10") (pinfunction "10_10") (pintype "passive"))
      (node (ref "P3") (pin "12") (pinfunction "12_12") (pintype "passive"))
      (node (ref "P3") (pin "14") (pinfunction "14_14") (pintype "passive"))
      (node (ref "P3") (pin "16") (pinfunction "16_16") (pintype "passive"))
      (node (ref "P3") (pin "18") (pinfunction "18_18") (pintype "passive"))
      (node (ref "P3") (pin "20") (pinfunction "20_20") (pintype "passive"))
      (node (ref "P3") (pin "4") (pinfunction "4_4") (pintype "passive"))
      (node (ref "P3") (pin "6") (pinfunction "6_6") (pintype "passive"))
      (node (ref "P3") (pin "8") (pinfunction "8_8") (pintype "passive"))
      (node (ref "P4") (pin "5") (pinfunction "5_5") (pintype "passive"))
      (node (ref "P4") (pin "6") (pinfunction "6_6") (pintype "passive"))
      (node (ref "P8") (pin "6") (pinfunction "VSS_6") (pintype "passive"))
      (node (ref "R15") (pin "1") (pinfunction "1_1") (pintype "passive"))
      (node (ref "R16") (pin "1") (pinfunction "1_1") (pintype "passive"))
      (node (ref "R17") (pin "1") (pinfunction "1_1") (pintype "passive"))
      (node (ref "R18") (pin "0") (pinfunction "0_0") (pintype "passive"))
      (node (ref "R19") (pin "0") (pinfunction "0_0") (pintype "passive"))
      (node (ref "R2") (pin "1") (pinfunction "1_1") (pintype "passive"))
      (node (ref "R22") (pin "1") (pinfunction "1_1") (pintype "passive"))
      (node (ref "R23") (pin "1") (pinfunction "1_1") (pintype "passive"))
      (node (ref "U1") (pin "1") (pinfunction "GND_1") (pintype "passive"))
      (node (ref "U2") (pin "23") (pinfunction "VSS_1_23") (pintype "power_in"))
      (node (ref "U2") (pin "35") (pinfunction "VSS_2_35") (pintype "power_in"))
      (node (ref "U2") (pin "47") (pinfunction "VSS_3_47") (pintype "power_in"))
      (node (ref "U2") (pin "8") (pinfunction "VSSA_8") (pintype "power_in"))
      (node (ref "U3") (pin "1") (pinfunction "GND_1") (pintype "passive"))
      (node (ref "U4") (pin "5") (pinfunction "GND_5") (pintype "passive"))
      (node (ref "U5") (pin "2") (pinfunction "GND_2") (pintype "passive"))
      (node (ref "U6") (pin "1") (pinfunction "CLKIN_1") (pintype "passive"))
      (node (ref "U6") (pin "11") (pinfunction "FSYNC_11") (pintype "passive"))
      (node (ref "U6") (pin "18") (pinfunction "GND_18") (pintype "passive"))
      (node (ref "U6") (pin "2") (pinfunction "NC_2") (pintype "passive"))
      (node (ref "U6") (pin "9") (pinfunction "AD0_9") (pintype "passive"))
      (node (ref "U7") (pin "11") (pinfunction "GND_11") (pintype "passive"))
      (node (ref "U7") (pin "7") (pinfunction "NC_7") (pintype "passive"))
      (node (ref "U7") (pin "9") (pinfunction "GND_9") (pintype "passive"))
      (node (ref "U8") (pin "3") (pinfunction "GND_3") (pintype "passive"))
      (node (ref "U8") (pin "4") (pinfunction "CSB_4") (pintype "passive"))
      (node (ref "U8") (pin "5") (pinfunction "CSB_5") (pintype "passive"))
    )
    (net (code "44") (name "Net-(L2-2)") (class "Default")
      (node (ref "L2") (pin "N") (pinfunction "2_N") (pintype "passive"))
      (node (ref "R22") (pin "0") (pinfunction "0_0") (pintype "passive"))
    )
    (net (code "45") (name "Net-(L3-2)") (class "Default")
      (node (ref "L3") (pin "N") (pinfunction "2_N") (pintype "passive"))
      (node (ref "R23") (pin "0") (pinfunction "0_0") (pintype "passive"))
    )
    (net (code "46") (name "Net-(M1-0)") (class "Default")
      (node (ref "M1") (pin "D") (pinfunction "0_D") (pintype "passive"))
      (node (ref "P5") (pin "2") (pinfunction "2_2") (pintype "passive"))
    )
    (net (code "47") (name "Net-(M2-0)") (class "Default")
      (node (ref "M2") (pin "D") (pinfunction "0_D") (pintype "passive"))
      (node (ref "P6") (pin "2") (pinfunction "2_2") (pintype "passive"))
    )
    (net (code "48") (name "Net-(M3-0)") (class "Default")
      (node (ref "M3") (pin "D") (pinfunction "0_D") (pintype "passive"))
      (node (ref "P9") (pin "2") (pinfunction "2_2") (pintype "passive"))
    )
    (net (code "49") (name "Net-(M4-0)") (class "Default")
      (node (ref "M4") (pin "D") (pinfunction "0_D") (pintype "passive"))
      (node (ref "P7") (pin "2") (pinfunction "2_2") (pintype "passive"))
    )
    (net (code "50") (name "Net-(P3-Pad11)") (class "Default")
      (node (ref "P3") (pin "11") (pinfunction "11_11") (pintype "passive"))
      (node (ref "R15") (pin "0") (pinfunction "0_0") (pintype "passive"))
    )
    (net (code "51") (name "Net-(U2A-PD0-OSC_IN)") (class "Default")
      (node (ref "C16") (pin "1") (pinfunction "1_1") (pintype "passive"))
      (node (ref "U2") (pin "5") (pinfunction "PD0-OSC_IN_5") (pintype "bidirectional"))
      (node (ref "X2") (pin "0") (pinfunction "0_0") (pintype "passive"))
    )
    (net (code "52") (name "Net-(U2A-PD1-OSC_OUT)") (class "Default")
      (node (ref "C20") (pin "1") (pinfunction "1_1") (pintype "passive"))
      (node (ref "U2") (pin "6") (pinfunction "PD1-OSC_OUT_6") (pintype "bidirectional"))
      (node (ref "X2") (pin "1") (pinfunction "1_1") (pintype "passive"))
    )
    (net (code "53") (name "Net-(U5-SW)") (class "Default")
      (node (ref "D1") (pin "P") (pinfunction "P_P") (pintype "passive"))
      (node (ref "L1") (pin "2") (pinfunction "2_2") (pintype "passive"))
      (node (ref "U5") (pin "1") (pinfunction "SW_1") (pintype "passive"))
    )
    (net (code "54") (name "Net-(U6-CPOUT)") (class "Default")
      (node (ref "C17") (pin "2") (pinfunction "2_2") (pintype "passive"))
      (node (ref "U6") (pin "20") (pinfunction "CPOUT_20") (pintype "passive"))
    )
    (net (code "55") (name "Net-(U6-REGOUT)") (class "Default")
      (node (ref "C23") (pin "1") (pinfunction "1_1") (pintype "passive"))
      (node (ref "U6") (pin "10") (pinfunction "REGOUT_10") (pintype "passive"))
    )
    (net (code "56") (name "Net-(U7-C1)") (class "Default")
      (node (ref "C18") (pin "1") (pinfunction "1_1") (pintype "passive"))
      (node (ref "U7") (pin "10") (pinfunction "C1_10") (pintype "passive"))
    )
    (net (code "57") (name "Net-(U7-SETC)") (class "Default")
      (node (ref "C19") (pin "2") (pinfunction "2_2") (pintype "passive"))
      (node (ref "U7") (pin "12") (pinfunction "SETC_12") (pintype "passive"))
    )
    (net (code "58") (name "Net-(U7-SETP)") (class "Default")
      (node (ref "C19") (pin "1") (pinfunction "1_1") (pintype "passive"))
      (node (ref "U7") (pin "8") (pinfunction "SETP_8") (pintype "passive"))
    )
    (net (code "59") (name "unconnected-(P3-Pad17)") (class "Default")
      (node (ref "P3") (pin "17") (pinfunction "17_17") (pintype "passive+no_connect"))
    )
    (net (code "60") (name "unconnected-(P3-Pad19)") (class "Default")
      (node (ref "P3") (pin "19") (pinfunction "19_19") (pintype "passive+no_connect"))
    )
    (net (code "61") (name "unconnected-(P8-RSV-Pad1)") (class "Default")
      (node (ref "P8") (pin "1") (pinfunction "RSV_1") (pintype "passive"))
    )
    (net (code "62") (name "unconnected-(P8-RSV-Pad8)") (class "Default")
      (node (ref "P8") (pin "8") (pinfunction "RSV_8") (pintype "passive"))
    )
    (net (code "63") (name "unconnected-(U2A-PA11-Pad32)") (class "Default")
      (node (ref "U2") (pin "32") (pinfunction "PA11_32") (pintype "bidirectional+no_connect"))
    )
    (net (code "64") (name "unconnected-(U2A-PB9-Pad46)") (class "Default")
      (node (ref "U2") (pin "46") (pinfunction "PB9_46") (pintype "bidirectional+no_connect"))
    )
    (net (code "65") (name "unconnected-(U2A-PC13-TAMPER-RTC-Pad2)") (class "Default")
      (node (ref "U2") (pin "2") (pinfunction "PC13-TAMPER-RTC_2") (pintype "bidirectional+no_connect"))
    )
    (net (code "66") (name "unconnected-(U2A-PC14-OSC32_IN-Pad3)") (class "Default")
      (node (ref "U2") (pin "3") (pinfunction "PC14-OSC32_IN_3") (pintype "bidirectional+no_connect"))
    )
    (net (code "67") (name "unconnected-(U2A-PC15-OSC32_OUT-Pad4)") (class "Default")
      (node (ref "U2") (pin "4") (pinfunction "PC15-OSC32_OUT_4") (pintype "bidirectional+no_connect"))
    )
    (net (code "68") (name "unconnected-(U3-CTS#-Pad9)") (class "Default")
      (node (ref "U3") (pin "9") (pinfunction "CTS#_9") (pintype "passive+no_connect"))
    )
    (net (code "69") (name "unconnected-(U3-DCD#-Pad12)") (class "Default")
      (node (ref "U3") (pin "12") (pinfunction "DCD#_12") (pintype "passive+no_connect"))
    )
    (net (code "70") (name "unconnected-(U3-DSR#-Pad10)") (class "Default")
      (node (ref "U3") (pin "10") (pinfunction "DSR#_10") (pintype "passive+no_connect"))
    )
    (net (code "71") (name "unconnected-(U3-DTR#-Pad13)") (class "Default")
      (node (ref "U3") (pin "13") (pinfunction "DTR#_13") (pintype "passive+no_connect"))
    )
    (net (code "72") (name "unconnected-(U3-R232-Pad15)") (class "Default")
      (node (ref "U3") (pin "15") (pinfunction "R232_15") (pintype "passive+no_connect"))
    )
    (net (code "73") (name "unconnected-(U3-RI#-Pad11)") (class "Default")
      (node (ref "U3") (pin "11") (pinfunction "RI#_11") (pintype "passive+no_connect"))
    )
    (net (code "74") (name "unconnected-(U3-RTS#-Pad14)") (class "Default")
      (node (ref "U3") (pin "14") (pinfunction "RTS#_14") (pintype "passive+no_connect"))
    )
    (net (code "75") (name "unconnected-(U4-ID-Pad4)") (class "Default")
      (node (ref "U4") (pin "4") (pinfunction "ID_4") (pintype "passive+no_connect"))
    )
    (net (code "76") (name "unconnected-(U6-NC-Pad3)") (class "Default")
      (node (ref "U6") (pin "3") (pinfunction "NC_3") (pintype "passive+no_connect"))
    )
    (net (code "77") (name "unconnected-(U6-NC-Pad4)") (class "Default")
      (node (ref "U6") (pin "4") (pinfunction "NC_4") (pintype "passive+no_connect"))
    )
    (net (code "78") (name "unconnected-(U6-NC-Pad5)") (class "Default")
      (node (ref "U6") (pin "5") (pinfunction "NC_5") (pintype "passive+no_connect"))
    )
    (net (code "79") (name "unconnected-(U6-NC-Pad16)") (class "Default")
      (node (ref "U6") (pin "16") (pinfunction "NC_16") (pintype "passive+no_connect"))
    )
    (net (code "80") (name "unconnected-(U6-NC-Pad17)") (class "Default")
      (node (ref "U6") (pin "17") (pinfunction "NC_17") (pintype "passive+no_connect"))
    )
    (net (code "81") (name "unconnected-(U6-RESV-Pad19)") (class "Default")
      (node (ref "U6") (pin "19") (pinfunction "RESV_19") (pintype "passive+no_connect"))
    )
    (net (code "82") (name "unconnected-(U6-RESV-Pad21)") (class "Default")
      (node (ref "U6") (pin "21") (pinfunction "RESV_21") (pintype "passive+no_connect"))
    )
    (net (code "83") (name "unconnected-(U6-RESV-Pad22)") (class "Default")
      (node (ref "U6") (pin "22") (pinfunction "RESV_22") (pintype "passive+no_connect"))
    )
    (net (code "84") (name "unconnected-(U7-NC-Pad3)") (class "Default")
      (node (ref "U7") (pin "3") (pinfunction "NC_3") (pintype "passive+no_connect"))
    )
    (net (code "85") (name "unconnected-(U7-NC-Pad5)") (class "Default")
      (node (ref "U7") (pin "5") (pinfunction "NC_5") (pintype "passive+no_connect"))
    )
    (net (code "86") (name "unconnected-(U7-NC-Pad6)") (class "Default")
      (node (ref "U7") (pin "6") (pinfunction "NC_6") (pintype "passive+no_connect"))
    )
    (net (code "87") (name "unconnected-(U7-NC-Pad14)") (class "Default")
      (node (ref "U7") (pin "14") (pinfunction "NC_14") (pintype "passive+no_connect"))
    )
  )
)
